# motherboard.net
KiCad netlist of a schematic drawn in EAGLE
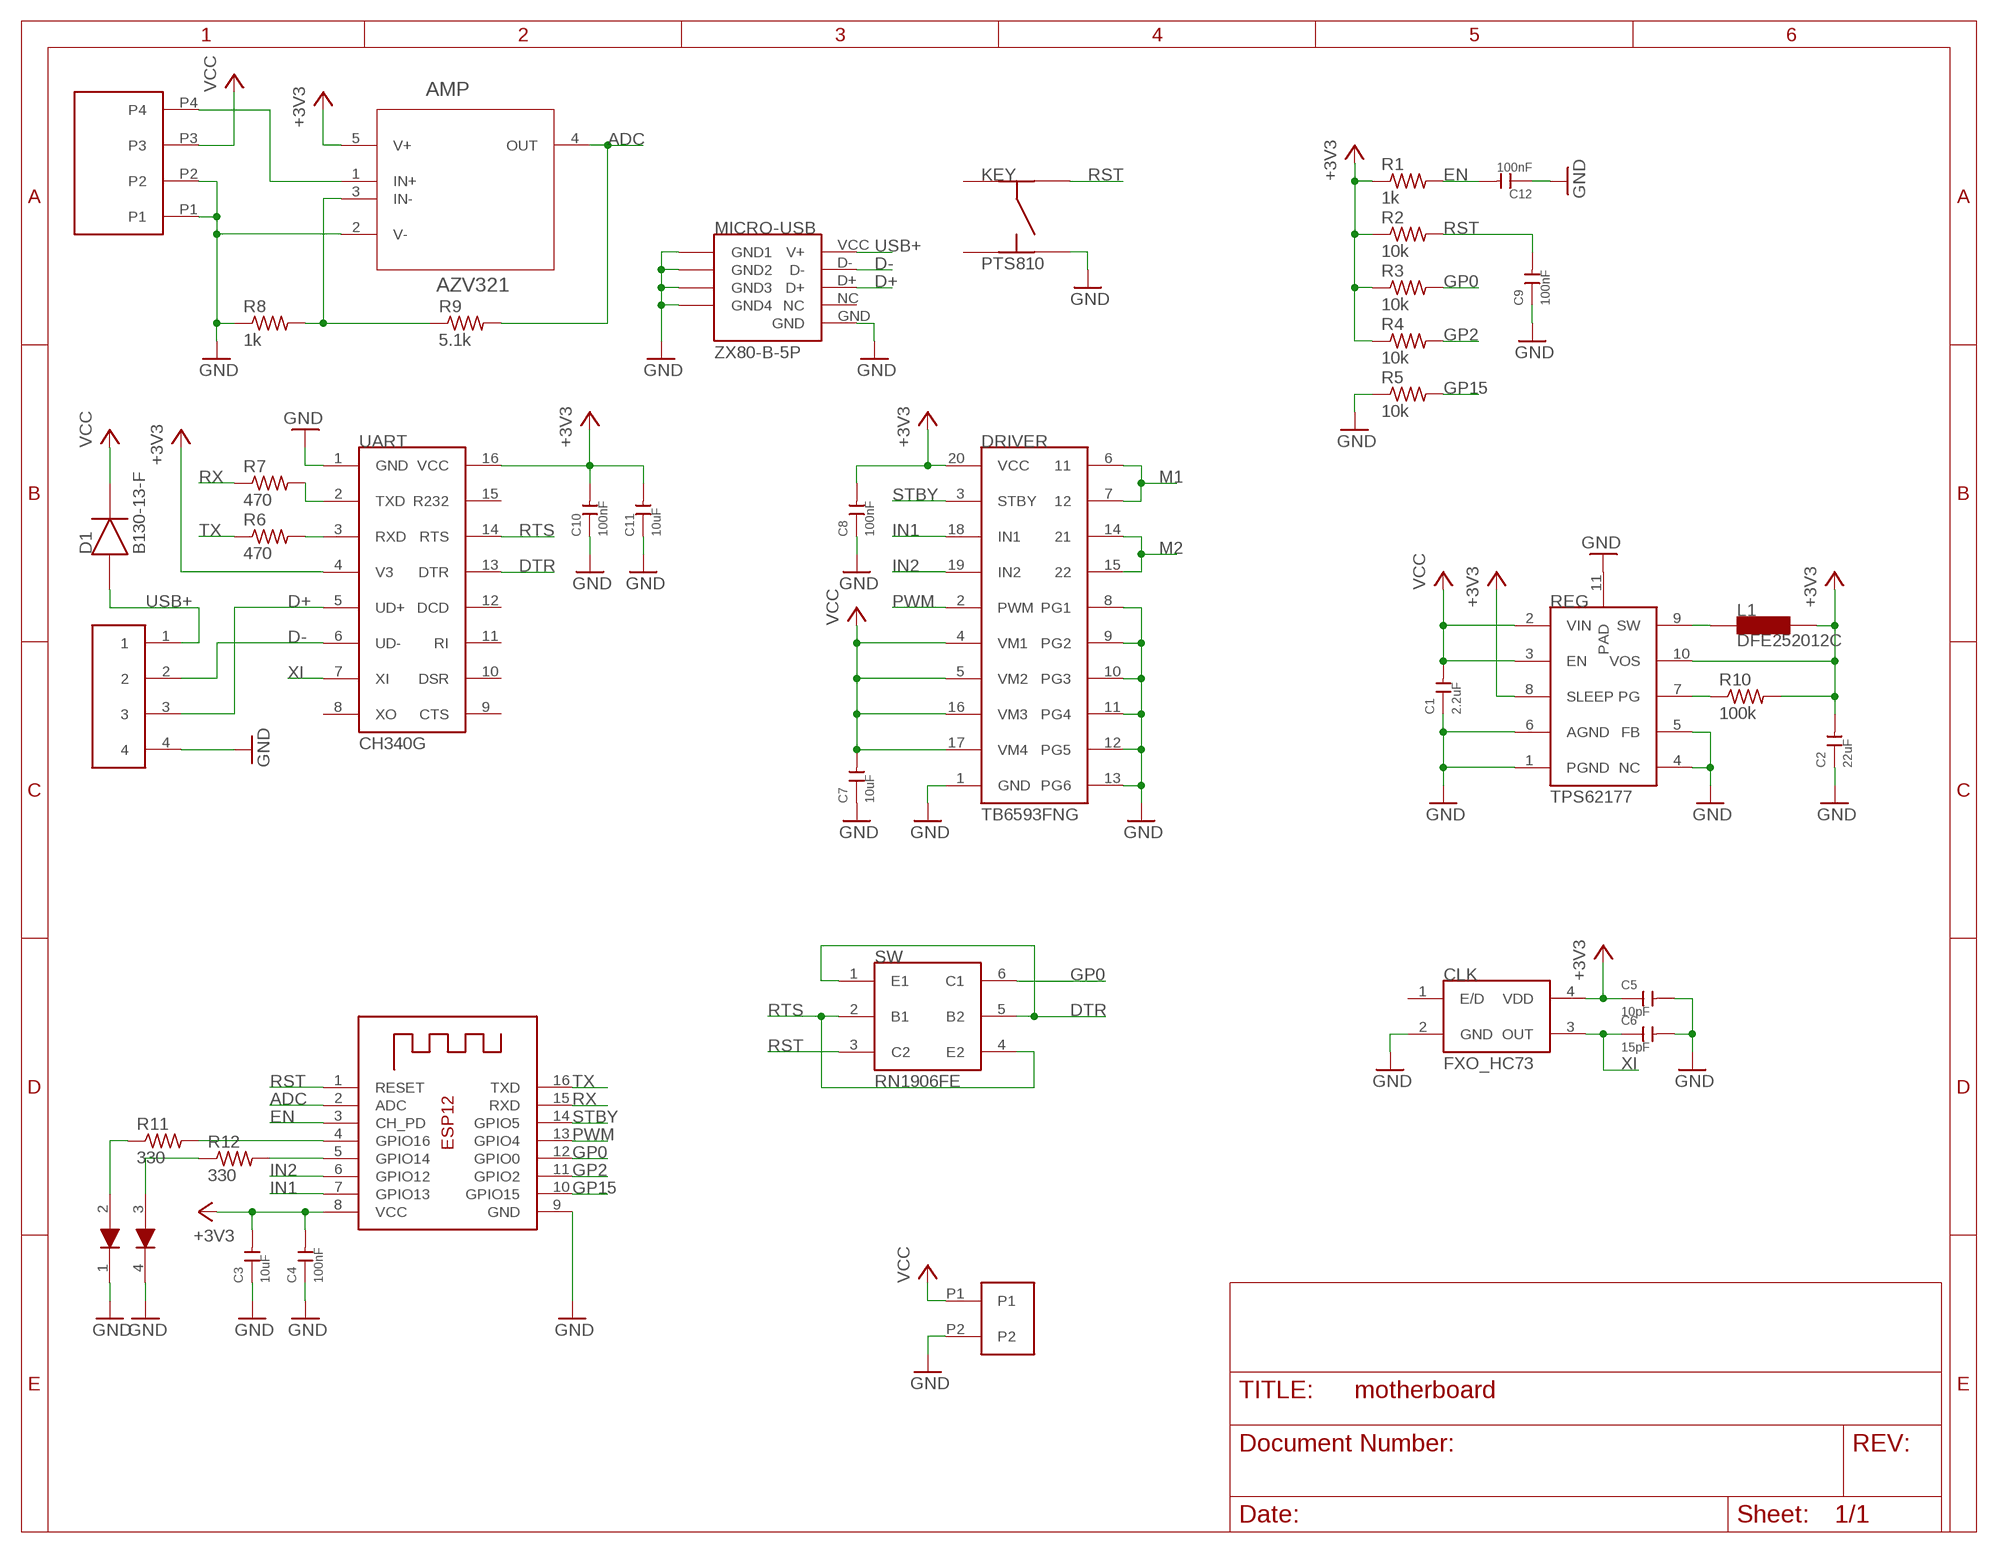
[diagram p0: schematic, sheet 1]

(export (version "E")
  (design (tool "Eeschema 10.0.6"))
  (components
    (comp (ref "AMP")
      (value "AZV321")
      (footprint "eagle-import:SOT65P210X110-5N")
      (fields (field (name "MPN") "LMV321SEG-7"))
      (libsource (lib "eagle-import") (part "LMV321SEG-7"))
    )
    (comp (ref "C1")
      (value "2.2uF")
      (footprint "eagle-import:C0603")
      (libsource (lib "eagle-import") (part "CERAMIC-0.5PF-50V-0.1PF-NPO(0603)"))
    )
    (comp (ref "C2")
      (value "22uF")
      (footprint "eagle-import:C0603")
      (libsource (lib "eagle-import") (part "CERAMIC-0.5PF-50V-0.1PF-NPO(0603)"))
    )
    (comp (ref "C3")
      (value "10uF")
      (footprint "eagle-import:C0603")
      (libsource (lib "eagle-import") (part "CERAMIC-0.5PF-50V-0.1PF-NPO(0603)"))
    )
    (comp (ref "C4")
      (value "100nF")
      (footprint "eagle-import:C0603")
      (libsource (lib "eagle-import") (part "CERAMIC-0.5PF-50V-0.1PF-NPO(0603)"))
    )
    (comp (ref "C5")
      (value "10pF")
      (footprint "eagle-import:C0603")
      (libsource (lib "eagle-import") (part "CERAMIC-0.5PF-50V-0.1PF-NPO(0603)"))
    )
    (comp (ref "C6")
      (value "15pF")
      (footprint "eagle-import:C0603")
      (libsource (lib "eagle-import") (part "CERAMIC-0.5PF-50V-0.1PF-NPO(0603)"))
    )
    (comp (ref "C7")
      (value "10uF")
      (footprint "eagle-import:C0603")
      (libsource (lib "eagle-import") (part "CERAMIC-0.5PF-50V-0.1PF-NPO(0603)"))
    )
    (comp (ref "C8")
      (value "100nF")
      (footprint "eagle-import:C0603")
      (libsource (lib "eagle-import") (part "CERAMIC-0.5PF-50V-0.1PF-NPO(0603)"))
    )
    (comp (ref "C9")
      (value "100nF")
      (footprint "eagle-import:C0603")
      (libsource (lib "eagle-import") (part "CERAMIC-1PF-50V-0.25PF-NPO(0603)"))
    )
    (comp (ref "C10")
      (value "100nF")
      (footprint "eagle-import:C0603")
      (libsource (lib "eagle-import") (part "CERAMIC-0.5PF-50V-0.1PF-NPO(0603)"))
    )
    (comp (ref "C11")
      (value "10uF")
      (footprint "eagle-import:C0603")
      (libsource (lib "eagle-import") (part "CERAMIC-0.5PF-50V-0.1PF-NPO(0603)"))
    )
    (comp (ref "C12")
      (value "100nF")
      (footprint "eagle-import:C0603")
      (libsource (lib "eagle-import") (part "CERAMIC-1PF-50V-0.25PF-NPO(0603)"))
    )
    (comp (ref "CLK")
      (value "FXO_HC73")
      (footprint "eagle-import:4-SMD")
      (libsource (lib "eagle-import") (part "FXO_HC73"))
    )
    (comp (ref "CONN")
      (value "BOURNS_2PIN")
      (footprint "eagle-import:BOURNS_2PIN")
      (libsource (lib "eagle-import") (part "BOURNS_2PIN"))
    )
    (comp (ref "D1")
      (value "B130-13-F")
      (footprint "eagle-import:SMA")
      (libsource (lib "eagle-import") (part "B130-13-F"))
    )
    (comp (ref "DRIVER")
      (value "TB6593FNG")
      (footprint "eagle-import:SSOP-20")
      (libsource (lib "eagle-import") (part "TB6593FNG"))
    )
    (comp (ref "ESP12")
      (value "ESP-12")
      (footprint "eagle-import:ESP-12")
      (libsource (lib "eagle-import") (part "ESP-12"))
    )
    (comp (ref "KEY")
      (value "PTS810")
      (footprint "eagle-import:BUTTON")
      (libsource (lib "eagle-import") (part "BUTTON"))
    )
    (comp (ref "L1")
      (value "DFE252012C")
      (footprint "eagle-import:1008")
      (libsource (lib "eagle-import") (part "DFE252012C"))
    )
    (comp (ref "MICRO-USB")
      (value "ZX80-B-5P")
      (footprint "eagle-import:USB_VERT")
      (libsource (lib "eagle-import") (part "USB_VERT"))
    )
    (comp (ref "R1")
      (value "1k")
      (footprint "eagle-import:R0603")
      (libsource (lib "eagle-import") (part "R-US_R0603"))
    )
    (comp (ref "R2")
      (value "10k")
      (footprint "eagle-import:R0603")
      (libsource (lib "eagle-import") (part "R-US_R0603"))
    )
    (comp (ref "R3")
      (value "10k")
      (footprint "eagle-import:R0603")
      (libsource (lib "eagle-import") (part "R-US_R0603"))
    )
    (comp (ref "R4")
      (value "10k")
      (footprint "eagle-import:R0603")
      (libsource (lib "eagle-import") (part "R-US_R0603"))
    )
    (comp (ref "R5")
      (value "10k")
      (footprint "eagle-import:R0603")
      (libsource (lib "eagle-import") (part "R-US_R0603"))
    )
    (comp (ref "R6")
      (value "470")
      (footprint "eagle-import:R0603")
      (libsource (lib "eagle-import") (part "R-US_R0603"))
    )
    (comp (ref "R7")
      (value "470")
      (footprint "eagle-import:R0603")
      (libsource (lib "eagle-import") (part "R-US_R0603"))
    )
    (comp (ref "R8")
      (value "1k")
      (footprint "eagle-import:R0603")
      (libsource (lib "eagle-import") (part "R-US_R0603"))
    )
    (comp (ref "R9")
      (value "5.1k")
      (footprint "eagle-import:R0603")
      (libsource (lib "eagle-import") (part "R-US_R0603"))
    )
    (comp (ref "R10")
      (value "100k")
      (footprint "eagle-import:R0603")
      (libsource (lib "eagle-import") (part "R-US_R0603"))
    )
    (comp (ref "R11")
      (value "330")
      (footprint "eagle-import:R0603")
      (libsource (lib "eagle-import") (part "R-US_R0603"))
    )
    (comp (ref "R12")
      (value "330")
      (footprint "eagle-import:R0603")
      (libsource (lib "eagle-import") (part "R-US_R0603"))
    )
    (comp (ref "REG")
      (value "TPS62177")
      (footprint "eagle-import:WSON-10")
      (libsource (lib "eagle-import") (part "TPS62177"))
    )
    (comp (ref "SW")
      (value "RN1906FE")
      (footprint "eagle-import:SOT-563")
      (libsource (lib "eagle-import") (part "RN1906FE"))
    )
    (comp (ref "U$2")
      (value "BI_LED")
      (footprint "eagle-import:BI_LED")
      (libsource (lib "eagle-import") (part "BI_LED"))
    )
    (comp (ref "U$3")
      (value "4PIN_HEADER")
      (footprint "eagle-import:4PIN_HEADER")
      (libsource (lib "eagle-import") (part "4PIN_HEADER"))
    )
    (comp (ref "UART")
      (value "CH340G")
      (footprint "eagle-import:20-16")
      (libsource (lib "eagle-import") (part "CH340G"))
    )
    (comp (ref "WIPER")
      (value "BOURNS_4PIN")
      (footprint "eagle-import:BOURNS_4PIN")
      (libsource (lib "eagle-import") (part "BOURNS_4PIN"))
    )
  )
  (nets
    (net (code "1") (name "+3V3") (class "Default")
      (node (ref "AMP") (pin "5") (pinfunction "V+_5") (pintype "power_in"))
      (node (ref "C10") (pin "2") (pinfunction "2_2") (pintype "passive"))
      (node (ref "C11") (pin "2") (pinfunction "2_2") (pintype "passive"))
      (node (ref "C2") (pin "2") (pinfunction "2_2") (pintype "passive"))
      (node (ref "C3") (pin "2") (pinfunction "2_2") (pintype "passive"))
      (node (ref "C4") (pin "2") (pinfunction "2_2") (pintype "passive"))
      (node (ref "C5") (pin "1") (pinfunction "1_1") (pintype "passive"))
      (node (ref "C8") (pin "2") (pinfunction "2_2") (pintype "passive"))
      (node (ref "CLK") (pin "4") (pinfunction "VDD_4") (pintype "bidirectional"))
      (node (ref "DRIVER") (pin "20") (pinfunction "VCC_20") (pintype "bidirectional"))
      (node (ref "ESP12") (pin "8") (pinfunction "VCC_8") (pintype "power_in"))
      (node (ref "L1") (pin "P$3") (pinfunction "P$2_P$3") (pintype "bidirectional"))
      (node (ref "R1") (pin "1") (pinfunction "1_1") (pintype "passive"))
      (node (ref "R10") (pin "2") (pinfunction "2_2") (pintype "passive"))
      (node (ref "R2") (pin "1") (pinfunction "1_1") (pintype "passive"))
      (node (ref "R3") (pin "1") (pinfunction "1_1") (pintype "passive"))
      (node (ref "R4") (pin "1") (pinfunction "1_1") (pintype "passive"))
      (node (ref "REG") (pin "10") (pinfunction "VOS_10") (pintype "bidirectional"))
      (node (ref "REG") (pin "8") (pinfunction "SLEEP_8") (pintype "bidirectional"))
      (node (ref "UART") (pin "16") (pinfunction "VCC_16") (pintype "bidirectional"))
      (node (ref "UART") (pin "4") (pinfunction "V3_4") (pintype "bidirectional"))
    )
    (net (code "2") (name "/ADC") (class "Default")
      (node (ref "AMP") (pin "4") (pinfunction "OUT_4") (pintype "output"))
      (node (ref "ESP12") (pin "2") (pinfunction "ADC_2") (pintype "passive"))
      (node (ref "R9") (pin "2") (pinfunction "2_2") (pintype "passive"))
    )
    (net (code "3") (name "/D+") (class "Default")
      (node (ref "MICRO-USB") (pin "D+") (pinfunction "D+_D+") (pintype "bidirectional"))
      (node (ref "U$3") (pin "3") (pinfunction "3_3") (pintype "bidirectional"))
      (node (ref "UART") (pin "5") (pinfunction "UD+_5") (pintype "bidirectional"))
    )
    (net (code "4") (name "/D-") (class "Default")
      (node (ref "MICRO-USB") (pin "D-") (pinfunction "D-_D-") (pintype "bidirectional"))
      (node (ref "U$3") (pin "2") (pinfunction "2_2") (pintype "bidirectional"))
      (node (ref "UART") (pin "6") (pinfunction "UD-_6") (pintype "bidirectional"))
    )
    (net (code "5") (name "/DTR") (class "Default")
      (node (ref "SW") (pin "1") (pinfunction "E1_1") (pintype "bidirectional"))
      (node (ref "SW") (pin "5") (pinfunction "B2_5") (pintype "bidirectional"))
      (node (ref "UART") (pin "13") (pinfunction "DTR_13") (pintype "bidirectional"))
    )
    (net (code "6") (name "/EN") (class "Default")
      (node (ref "C12") (pin "2") (pinfunction "2_2") (pintype "passive"))
      (node (ref "ESP12") (pin "3") (pinfunction "CH_PD_3") (pintype "input"))
      (node (ref "R1") (pin "2") (pinfunction "2_2") (pintype "passive"))
    )
    (net (code "7") (name "/GP0") (class "Default")
      (node (ref "ESP12") (pin "12") (pinfunction "GPIO0_12") (pintype "bidirectional"))
      (node (ref "R3") (pin "2") (pinfunction "2_2") (pintype "passive"))
      (node (ref "SW") (pin "6") (pinfunction "C1_6") (pintype "bidirectional"))
    )
    (net (code "8") (name "/GP2") (class "Default")
      (node (ref "ESP12") (pin "11") (pinfunction "GPIO2_11") (pintype "bidirectional"))
      (node (ref "R4") (pin "2") (pinfunction "2_2") (pintype "passive"))
    )
    (net (code "9") (name "/GP15") (class "Default")
      (node (ref "ESP12") (pin "10") (pinfunction "GPIO15_10") (pintype "bidirectional"))
      (node (ref "R5") (pin "2") (pinfunction "2_2") (pintype "passive"))
    )
    (net (code "10") (name "/IN1") (class "Default")
      (node (ref "DRIVER") (pin "18") (pinfunction "IN1_18") (pintype "bidirectional"))
      (node (ref "ESP12") (pin "7") (pinfunction "GPIO13_7") (pintype "bidirectional"))
    )
    (net (code "11") (name "/IN2") (class "Default")
      (node (ref "DRIVER") (pin "19") (pinfunction "IN2_19") (pintype "bidirectional"))
      (node (ref "ESP12") (pin "6") (pinfunction "GPIO12_6") (pintype "bidirectional"))
    )
    (net (code "12") (name "/M1") (class "Default")
      (node (ref "DRIVER") (pin "6") (pinfunction "11_6") (pintype "bidirectional"))
      (node (ref "DRIVER") (pin "7") (pinfunction "12_7") (pintype "bidirectional"))
    )
    (net (code "13") (name "/M2") (class "Default")
      (node (ref "DRIVER") (pin "14") (pinfunction "21_14") (pintype "bidirectional"))
      (node (ref "DRIVER") (pin "15") (pinfunction "22_15") (pintype "bidirectional"))
    )
    (net (code "14") (name "/PWM") (class "Default")
      (node (ref "DRIVER") (pin "2") (pinfunction "PWM_2") (pintype "bidirectional"))
      (node (ref "ESP12") (pin "13") (pinfunction "GPIO4_13") (pintype "bidirectional"))
    )
    (net (code "15") (name "/RST") (class "Default")
      (node (ref "C9") (pin "2") (pinfunction "2_2") (pintype "passive"))
      (node (ref "ESP12") (pin "1") (pinfunction "RESET_1") (pintype "input"))
      (node (ref "KEY") (pin "2") (pinfunction "2_2") (pintype "bidirectional"))
      (node (ref "R2") (pin "2") (pinfunction "2_2") (pintype "passive"))
      (node (ref "SW") (pin "3") (pinfunction "C2_3") (pintype "bidirectional"))
    )
    (net (code "16") (name "/RTS") (class "Default")
      (node (ref "SW") (pin "2") (pinfunction "B1_2") (pintype "bidirectional"))
      (node (ref "SW") (pin "4") (pinfunction "E2_4") (pintype "bidirectional"))
      (node (ref "UART") (pin "14") (pinfunction "RTS_14") (pintype "bidirectional"))
    )
    (net (code "17") (name "/RX") (class "Default")
      (node (ref "ESP12") (pin "15") (pinfunction "RXD_15") (pintype "input"))
      (node (ref "R7") (pin "1") (pinfunction "1_1") (pintype "passive"))
    )
    (net (code "18") (name "/STBY") (class "Default")
      (node (ref "DRIVER") (pin "3") (pinfunction "STBY_3") (pintype "bidirectional"))
      (node (ref "ESP12") (pin "14") (pinfunction "GPIO5_14") (pintype "bidirectional"))
    )
    (net (code "19") (name "/TX") (class "Default")
      (node (ref "ESP12") (pin "16") (pinfunction "TXD_16") (pintype "output"))
      (node (ref "R6") (pin "1") (pinfunction "1_1") (pintype "passive"))
    )
    (net (code "20") (name "/USB+") (class "Default")
      (node (ref "D1") (pin "AN") (pinfunction "AN_AN") (pintype "bidirectional"))
      (node (ref "MICRO-USB") (pin "VCC") (pinfunction "V+_VCC") (pintype "bidirectional"))
      (node (ref "U$3") (pin "1") (pinfunction "1_1") (pintype "bidirectional"))
    )
    (net (code "21") (name "/XI") (class "Default")
      (node (ref "C6") (pin "1") (pinfunction "1_1") (pintype "passive"))
      (node (ref "CLK") (pin "3") (pinfunction "OUT_3") (pintype "bidirectional"))
      (node (ref "UART") (pin "7") (pinfunction "XI_7") (pintype "bidirectional"))
    )
    (net (code "22") (name "GND") (class "Default")
      (node (ref "AMP") (pin "2") (pinfunction "V-_2") (pintype "power_in"))
      (node (ref "C1") (pin "1") (pinfunction "1_1") (pintype "passive"))
      (node (ref "C10") (pin "1") (pinfunction "1_1") (pintype "passive"))
      (node (ref "C11") (pin "1") (pinfunction "1_1") (pintype "passive"))
      (node (ref "C12") (pin "1") (pinfunction "1_1") (pintype "passive"))
      (node (ref "C2") (pin "1") (pinfunction "1_1") (pintype "passive"))
      (node (ref "C3") (pin "1") (pinfunction "1_1") (pintype "passive"))
      (node (ref "C4") (pin "1") (pinfunction "1_1") (pintype "passive"))
      (node (ref "C5") (pin "2") (pinfunction "2_2") (pintype "passive"))
      (node (ref "C6") (pin "2") (pinfunction "2_2") (pintype "passive"))
      (node (ref "C7") (pin "1") (pinfunction "1_1") (pintype "passive"))
      (node (ref "C8") (pin "1") (pinfunction "1_1") (pintype "passive"))
      (node (ref "C9") (pin "1") (pinfunction "1_1") (pintype "passive"))
      (node (ref "CLK") (pin "2") (pinfunction "GND_2") (pintype "bidirectional"))
      (node (ref "CONN") (pin "P2") (pinfunction "P2_P2") (pintype "bidirectional"))
      (node (ref "DRIVER") (pin "1") (pinfunction "GND_1") (pintype "bidirectional"))
      (node (ref "DRIVER") (pin "10") (pinfunction "PG3_10") (pintype "bidirectional"))
      (node (ref "DRIVER") (pin "11") (pinfunction "PG4_11") (pintype "bidirectional"))
      (node (ref "DRIVER") (pin "12") (pinfunction "PG5_12") (pintype "bidirectional"))
      (node (ref "DRIVER") (pin "13") (pinfunction "PG6_13") (pintype "bidirectional"))
      (node (ref "DRIVER") (pin "8") (pinfunction "PG1_8") (pintype "bidirectional"))
      (node (ref "DRIVER") (pin "9") (pinfunction "PG2_9") (pintype "bidirectional"))
      (node (ref "ESP12") (pin "9") (pinfunction "GND_9") (pintype "power_in"))
      (node (ref "KEY") (pin "4") (pinfunction "4_4") (pintype "bidirectional"))
      (node (ref "MICRO-USB") (pin "GND") (pinfunction "GND_GND") (pintype "bidirectional"))
      (node (ref "MICRO-USB") (pin "GND1") (pinfunction "GND1_GND1") (pintype "bidirectional"))
      (node (ref "MICRO-USB") (pin "GND2") (pinfunction "GND2_GND2") (pintype "bidirectional"))
      (node (ref "MICRO-USB") (pin "GND3") (pinfunction "GND3_GND3") (pintype "bidirectional"))
      (node (ref "MICRO-USB") (pin "GND4") (pinfunction "GND4_GND4") (pintype "bidirectional"))
      (node (ref "R5") (pin "1") (pinfunction "1_1") (pintype "passive"))
      (node (ref "R8") (pin "1") (pinfunction "1_1") (pintype "passive"))
      (node (ref "REG") (pin "1") (pinfunction "PGND_1") (pintype "bidirectional"))
      (node (ref "REG") (pin "11") (pinfunction "PAD_11") (pintype "bidirectional"))
      (node (ref "REG") (pin "4") (pinfunction "NC_4") (pintype "bidirectional"))
      (node (ref "REG") (pin "5") (pinfunction "FB_5") (pintype "bidirectional"))
      (node (ref "REG") (pin "6") (pinfunction "AGND_6") (pintype "bidirectional"))
      (node (ref "U$2") (pin "1") (pinfunction "1_1") (pintype "bidirectional"))
      (node (ref "U$2") (pin "4") (pinfunction "4_4") (pintype "bidirectional"))
      (node (ref "U$3") (pin "4") (pinfunction "4_4") (pintype "bidirectional"))
      (node (ref "UART") (pin "1") (pinfunction "GND_1") (pintype "bidirectional"))
      (node (ref "WIPER") (pin "P1") (pinfunction "P1_P1") (pintype "bidirectional"))
      (node (ref "WIPER") (pin "P2") (pinfunction "P2_P2") (pintype "bidirectional"))
    )
    (net (code "23") (name "Net-(AMP-IN+)") (class "Default")
      (node (ref "AMP") (pin "1") (pinfunction "IN+_1") (pintype "input"))
      (node (ref "WIPER") (pin "P4") (pinfunction "P4_P4") (pintype "bidirectional"))
    )
    (net (code "24") (name "Net-(AMP-IN-)") (class "Default")
      (node (ref "AMP") (pin "3") (pinfunction "IN-_3") (pintype "input"))
      (node (ref "R8") (pin "2") (pinfunction "2_2") (pintype "passive"))
      (node (ref "R9") (pin "1") (pinfunction "1_1") (pintype "passive"))
    )
    (net (code "25") (name "Net-(ESP12-GPIO14)") (class "Default")
      (node (ref "ESP12") (pin "5") (pinfunction "GPIO14_5") (pintype "bidirectional"))
      (node (ref "R12") (pin "2") (pinfunction "2_2") (pintype "passive"))
    )
    (net (code "26") (name "Net-(ESP12-GPIO16)") (class "Default")
      (node (ref "ESP12") (pin "4") (pinfunction "GPIO16_4") (pintype "bidirectional"))
      (node (ref "R11") (pin "2") (pinfunction "2_2") (pintype "passive"))
    )
    (net (code "27") (name "Net-(L1-P$1)") (class "Default")
      (node (ref "L1") (pin "P$2") (pinfunction "P$1_P$2") (pintype "bidirectional"))
      (node (ref "REG") (pin "9") (pinfunction "SW_9") (pintype "bidirectional"))
    )
    (net (code "28") (name "Net-(R11-Pad1)") (class "Default")
      (node (ref "R11") (pin "1") (pinfunction "1_1") (pintype "passive"))
      (node (ref "U$2") (pin "2") (pinfunction "2_2") (pintype "bidirectional"))
    )
    (net (code "29") (name "Net-(R12-Pad1)") (class "Default")
      (node (ref "R12") (pin "1") (pinfunction "1_1") (pintype "passive"))
      (node (ref "U$2") (pin "3") (pinfunction "3_3") (pintype "bidirectional"))
    )
    (net (code "30") (name "Net-(REG-PG)") (class "Default")
      (node (ref "R10") (pin "1") (pinfunction "1_1") (pintype "passive"))
      (node (ref "REG") (pin "7") (pinfunction "PG_7") (pintype "bidirectional"))
    )
    (net (code "31") (name "Net-(UART-RXD)") (class "Default")
      (node (ref "R6") (pin "2") (pinfunction "2_2") (pintype "passive"))
      (node (ref "UART") (pin "3") (pinfunction "RXD_3") (pintype "bidirectional"))
    )
    (net (code "32") (name "Net-(UART-TXD)") (class "Default")
      (node (ref "R7") (pin "2") (pinfunction "2_2") (pintype "passive"))
      (node (ref "UART") (pin "2") (pinfunction "TXD_2") (pintype "bidirectional"))
    )
    (net (code "33") (name "VCC") (class "Default")
      (node (ref "C1") (pin "2") (pinfunction "2_2") (pintype "passive"))
      (node (ref "C7") (pin "2") (pinfunction "2_2") (pintype "passive"))
      (node (ref "CONN") (pin "P1") (pinfunction "P1_P1") (pintype "bidirectional"))
      (node (ref "D1") (pin "CATH") (pinfunction "CATH_CATH") (pintype "bidirectional"))
      (node (ref "DRIVER") (pin "16") (pinfunction "VM3_16") (pintype "bidirectional"))
      (node (ref "DRIVER") (pin "17") (pinfunction "VM4_17") (pintype "bidirectional"))
      (node (ref "DRIVER") (pin "4") (pinfunction "VM1_4") (pintype "bidirectional"))
      (node (ref "DRIVER") (pin "5") (pinfunction "VM2_5") (pintype "bidirectional"))
      (node (ref "REG") (pin "2") (pinfunction "VIN_2") (pintype "bidirectional"))
      (node (ref "REG") (pin "3") (pinfunction "EN_3") (pintype "bidirectional"))
      (node (ref "WIPER") (pin "P3") (pinfunction "P3_P3") (pintype "bidirectional"))
    )
    (net (code "34") (name "unconnected-(CLK-E{slash}D-Pad1)") (class "Default")
      (node (ref "CLK") (pin "1") (pinfunction "E/D_1") (pintype "bidirectional"))
    )
    (net (code "35") (name "unconnected-(KEY-Pad1)") (class "Default")
      (node (ref "KEY") (pin "1") (pinfunction "1_1") (pintype "bidirectional"))
    )
    (net (code "36") (name "unconnected-(KEY-Pad3)") (class "Default")
      (node (ref "KEY") (pin "3") (pinfunction "3_3") (pintype "bidirectional"))
    )
    (net (code "37") (name "unconnected-(MICRO-USB-PadNC)") (class "Default")
      (node (ref "MICRO-USB") (pin "NC") (pinfunction "NC_NC") (pintype "bidirectional"))
    )
    (net (code "38") (name "unconnected-(UART-CTS-Pad9)") (class "Default")
      (node (ref "UART") (pin "9") (pinfunction "CTS_9") (pintype "bidirectional"))
    )
    (net (code "39") (name "unconnected-(UART-DCD-Pad12)") (class "Default")
      (node (ref "UART") (pin "12") (pinfunction "DCD_12") (pintype "bidirectional"))
    )
    (net (code "40") (name "unconnected-(UART-DSR-Pad10)") (class "Default")
      (node (ref "UART") (pin "10") (pinfunction "DSR_10") (pintype "bidirectional"))
    )
    (net (code "41") (name "unconnected-(UART-R232-Pad15)") (class "Default")
      (node (ref "UART") (pin "15") (pinfunction "R232_15") (pintype "bidirectional"))
    )
    (net (code "42") (name "unconnected-(UART-RI-Pad11)") (class "Default")
      (node (ref "UART") (pin "11") (pinfunction "RI_11") (pintype "bidirectional"))
    )
    (net (code "43") (name "unconnected-(UART-XO-Pad8)") (class "Default")
      (node (ref "UART") (pin "8") (pinfunction "XO_8") (pintype "bidirectional"))
    )
  )
)
